# WorkLamp.net
KiCad netlist of a schematic drawn in Altium Designer
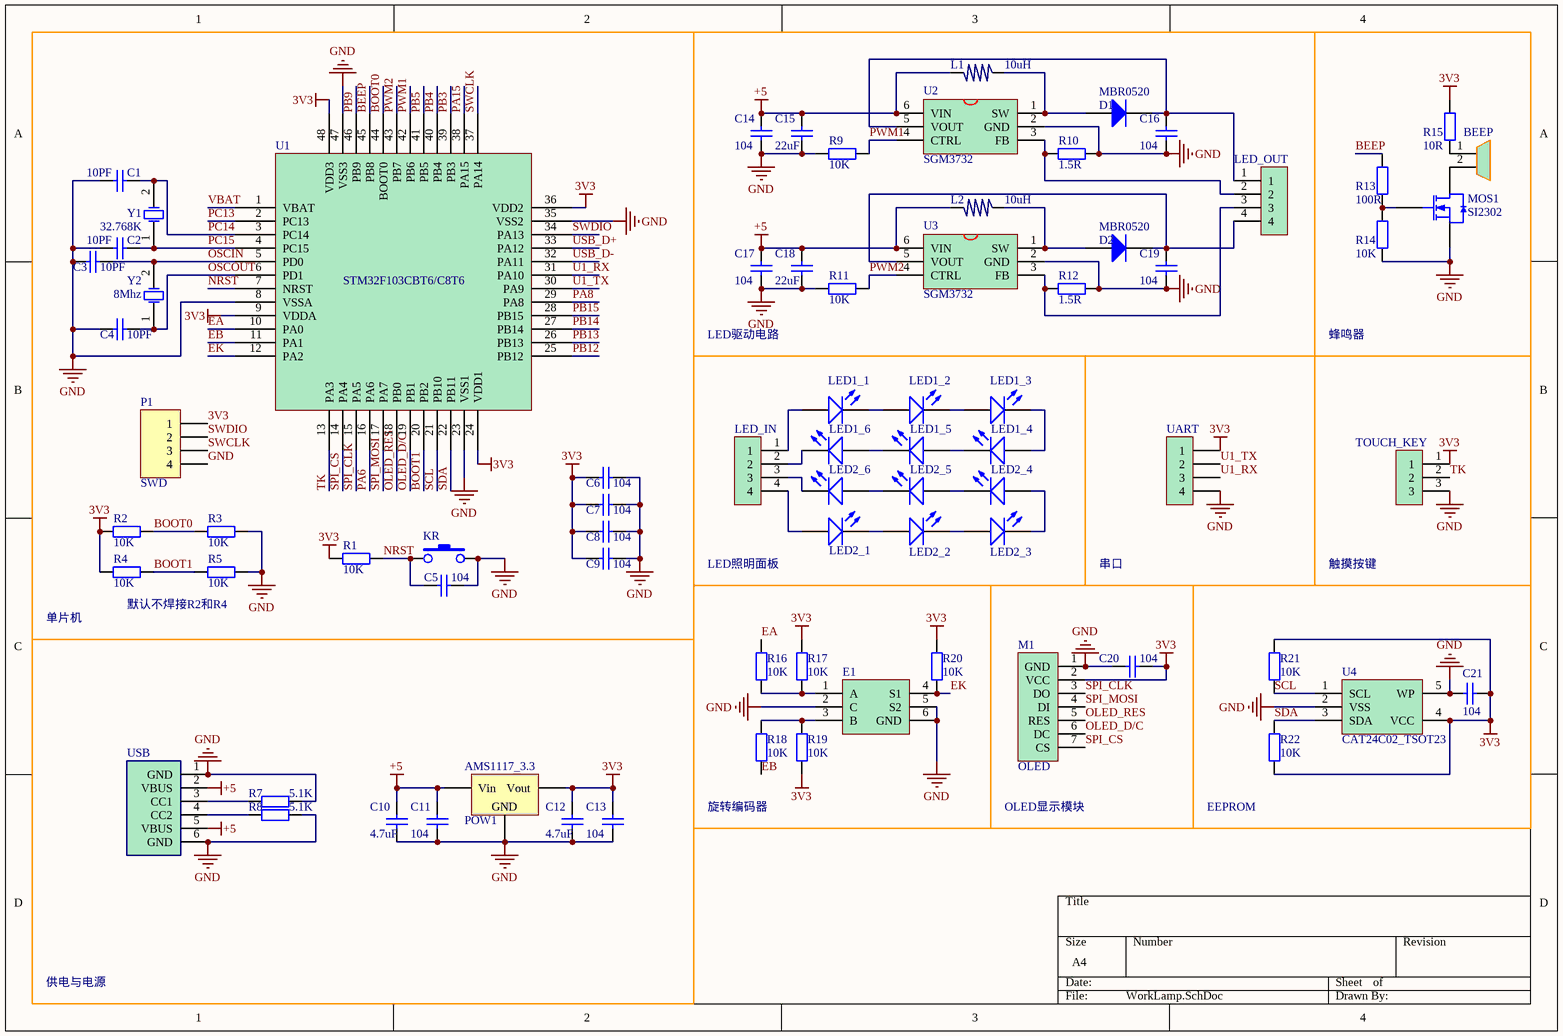
[diagram p0: WorkLamp.SchDoc]

(export (version "E")
  (design (tool "Eeschema 10.0.6"))
  (components
    (comp (ref "BEEP")
      (value "BEEP_5020_SMT")
      (footprint "BEEP_5020_SMT")
      (libsource (lib "MT_Device") (part "BEEP_5020_SMT"))
    )
    (comp (ref "C1") (value "10PF") (footprint "0603_C") (libsource (lib "MT_Device") (part "0603_CAP")))
    (comp (ref "C2") (value "10PF") (footprint "0603_C") (libsource (lib "MT_Device") (part "0603_CAP")))
    (comp (ref "C3") (value "10PF") (footprint "0603_C") (libsource (lib "MT_Device") (part "0603_CAP")))
    (comp (ref "C4") (value "10PF") (footprint "0603_C") (libsource (lib "MT_Device") (part "0603_CAP")))
    (comp (ref "C5") (value "104") (footprint "0603_C") (libsource (lib "MT_Device") (part "0603_CAP")))
    (comp (ref "C6") (value "104") (footprint "0603_C") (libsource (lib "MT_Device") (part "0603_CAP")))
    (comp (ref "C7") (value "104") (footprint "0603_C") (libsource (lib "MT_Device") (part "0603_CAP")))
    (comp (ref "C8") (value "104") (footprint "0603_C") (libsource (lib "MT_Device") (part "0603_CAP")))
    (comp (ref "C9") (value "104") (footprint "0603_C") (libsource (lib "MT_Device") (part "0603_CAP")))
    (comp (ref "C10") (value "4.7uF") (footprint "0603_C") (libsource (lib "MT_Device") (part "0603_CAP")))
    (comp (ref "C11") (value "104") (footprint "0603_C") (libsource (lib "MT_Device") (part "0603_CAP")))
    (comp (ref "C12") (value "4.7uF") (footprint "0603_C") (libsource (lib "MT_Device") (part "0603_CAP")))
    (comp (ref "C13") (value "104") (footprint "0603_C") (libsource (lib "MT_Device") (part "0603_CAP")))
    (comp (ref "C14") (value "104") (footprint "0603_C") (libsource (lib "MT_Device") (part "0603_CAP")))
    (comp (ref "C15") (value "22uF") (footprint "0603_C") (libsource (lib "MT_Device") (part "0603_CAP")))
    (comp (ref "C16") (value "104") (footprint "0603_C") (libsource (lib "MT_Device") (part "0603_CAP")))
    (comp (ref "C17") (value "104") (footprint "0603_C") (libsource (lib "MT_Device") (part "0603_CAP")))
    (comp (ref "C18") (value "22uF") (footprint "0603_C") (libsource (lib "MT_Device") (part "0603_CAP")))
    (comp (ref "C19") (value "104") (footprint "0603_C") (libsource (lib "MT_Device") (part "0603_CAP")))
    (comp (ref "C20") (value "104") (footprint "0603_C") (libsource (lib "MT_Device") (part "0603_CAP")))
    (comp (ref "C21") (value "104") (footprint "0603_C") (libsource (lib "MT_Device") (part "0603_CAP")))
    (comp (ref "D1")
      (value "MBR0520")
      (footprint "SOD_123")
      (libsource (lib "MT_Device") (part "SOD123_MBR0520"))
    )
    (comp (ref "D2")
      (value "MBR0520")
      (footprint "SOD_123")
      (libsource (lib "MT_Device") (part "SOD123_MBR0520"))
    )
    (comp (ref "E1")
      (value "ENCODER")
      (footprint "ENCODER_EC11_DIP")
      (libsource (lib "MT_Device") (part "ENCODER_EC11_DIP"))
    )
    (comp (ref "KR") (value "KEY_SMT") (footprint "KEY_SMT") (libsource (lib "MT_Device") (part "KEY_SMT")))
    (comp (ref "L1") (value "10uH") (footprint "0630_L") (libsource (lib "MT_Device") (part "0630_L")))
    (comp (ref "L2") (value "10uH") (footprint "0630_L") (libsource (lib "MT_Device") (part "0630_L")))
    (comp (ref "LED1_1")
      (value "LED_5730")
      (footprint "LED_5730")
      (description "LED 5730")
      (libsource (lib "MT_Device") (part "LED_5730"))
    )
    (comp (ref "LED1_2")
      (value "LED_5730")
      (footprint "LED_5730")
      (description "LED 5730")
      (libsource (lib "MT_Device") (part "LED_5730"))
    )
    (comp (ref "LED1_3")
      (value "LED_5730")
      (footprint "LED_5730")
      (description "LED 5730")
      (libsource (lib "MT_Device") (part "LED_5730"))
    )
    (comp (ref "LED1_4")
      (value "LED_5730")
      (footprint "LED_5730")
      (description "LED 5730")
      (libsource (lib "MT_Device") (part "LED_5730"))
    )
    (comp (ref "LED1_5")
      (value "LED_5730")
      (footprint "LED_5730")
      (description "LED 5730")
      (libsource (lib "MT_Device") (part "LED_5730"))
    )
    (comp (ref "LED1_6")
      (value "LED_5730")
      (footprint "LED_5730")
      (description "LED 5730")
      (libsource (lib "MT_Device") (part "LED_5730"))
    )
    (comp (ref "LED2_1")
      (value "LED_5730")
      (footprint "LED_5730")
      (description "LED 5730")
      (libsource (lib "MT_Device") (part "LED_5730"))
    )
    (comp (ref "LED2_2")
      (value "LED_5730")
      (footprint "LED_5730")
      (description "LED 5730")
      (libsource (lib "MT_Device") (part "LED_5730"))
    )
    (comp (ref "LED2_3")
      (value "LED_5730")
      (footprint "LED_5730")
      (description "LED 5730")
      (libsource (lib "MT_Device") (part "LED_5730"))
    )
    (comp (ref "LED2_4")
      (value "LED_5730")
      (footprint "LED_5730")
      (description "LED 5730")
      (libsource (lib "MT_Device") (part "LED_5730"))
    )
    (comp (ref "LED2_5")
      (value "LED_5730")
      (footprint "LED_5730")
      (description "LED 5730")
      (libsource (lib "MT_Device") (part "LED_5730"))
    )
    (comp (ref "LED2_6")
      (value "LED_5730")
      (footprint "LED_5730")
      (description "LED 5730")
      (libsource (lib "MT_Device") (part "LED_5730"))
    )
    (comp (ref "LED_IN")
      (value "SH1.25mm_4P")
      (footprint "SH1.25MM_4P")
      (libsource (lib "MT_Connector") (part "SH1.25mm_4P"))
    )
    (comp (ref "LED_OUT")
      (value "SH1.25mm_4P")
      (footprint "SH1.25MM_4P")
      (libsource (lib "") (part "SH1.25mm_4P_1"))
    )
    (comp (ref "M1")
      (value "OLED")
      (footprint "OLED_0.96_SPI")
      (libsource (lib "MT_Module") (part "OLED_0.96_SPI"))
    )
    (comp (ref "MOS1")
      (value "SI2302")
      (footprint "SOT23")
      (libsource (lib "MT_Device") (part "MOSN_SI2302_SOT23"))
    )
    (comp (ref "P1")
      (value "SWD")
      (footprint "HDR1X4")
      (description "Header, 4-Pin")
      (fields (field (name "PUBLISHER") "Altium Limited"))
      (libsource (lib "Miscellaneous Connectors") (part "Header 4"))
    )
    (comp (ref "POW1")
      (value "AMS1117_3.3")
      (footprint "SOT223")
      (libsource (lib "MT_Device") (part "AMS1117_3.3"))
    )
    (comp (ref "R1") (value "10K") (footprint "0603_R") (libsource (lib "") (part "0603_RES_2")))
    (comp (ref "R2") (value "10K") (footprint "0603_R") (libsource (lib "MT_Device") (part "0603_RES")))
    (comp (ref "R3") (value "10K") (footprint "0603_R") (libsource (lib "MT_Device") (part "0603_RES")))
    (comp (ref "R4") (value "10K") (footprint "0603_R") (libsource (lib "MT_Device") (part "0603_RES")))
    (comp (ref "R5") (value "10K") (footprint "0603_R") (libsource (lib "MT_Device") (part "0603_RES")))
    (comp (ref "R7") (value "5.1K") (footprint "0603_R") (libsource (lib "MT_Device") (part "0603_RES")))
    (comp (ref "R8") (value "5.1K") (footprint "0603_R") (libsource (lib "MT_Device") (part "0603_RES")))
    (comp (ref "R9") (value "10K") (footprint "0603_R") (libsource (lib "") (part "0603_RES_2")))
    (comp (ref "R10") (value "1.5R") (footprint "0603_R") (libsource (lib "MT_Device") (part "0603_RES")))
    (comp (ref "R11") (value "10K") (footprint "0603_R") (libsource (lib "") (part "0603_RES_2")))
    (comp (ref "R12") (value "1.5R") (footprint "0603_R") (libsource (lib "MT_Device") (part "0603_RES")))
    (comp (ref "R13") (value "100R") (footprint "0603_R") (libsource (lib "") (part "0603_RES_1")))
    (comp (ref "R14") (value "10K") (footprint "0603_R") (libsource (lib "") (part "0603_RES_1")))
    (comp (ref "R15") (value "10R") (footprint "0603_R") (libsource (lib "") (part "0603_RES_3")))
    (comp (ref "R16") (value "10K") (footprint "0603_R") (libsource (lib "") (part "0603_RES_1")))
    (comp (ref "R17") (value "10K") (footprint "0603_R") (libsource (lib "") (part "0603_RES_1")))
    (comp (ref "R18") (value "10K") (footprint "0603_R") (libsource (lib "") (part "0603_RES_1")))
    (comp (ref "R19") (value "10K") (footprint "0603_R") (libsource (lib "") (part "0603_RES_1")))
    (comp (ref "R20") (value "10K") (footprint "0603_R") (libsource (lib "") (part "0603_RES_1")))
    (comp (ref "R21") (value "10K") (footprint "0603_R") (libsource (lib "") (part "0603_RES_1")))
    (comp (ref "R22") (value "10K") (footprint "0603_R") (libsource (lib "") (part "0603_RES_1")))
    (comp (ref "TOUCH_KEY")
      (value "SH1.25mm_3P")
      (footprint "SH1.25mm_3P")
      (libsource (lib "MT_Connector") (part "SH1.25mm_3P"))
    )
    (comp (ref "U1")
      (value "STM32F103C8T6")
      (footprint "LQFP48")
      (libsource (lib "MT_Chip") (part "STM32F103C8T6"))
    )
    (comp (ref "U2")
      (value "SGM3732")
      (footprint "TSOT_23_6")
      (description "PWM Dimming, 38V Step-Up LED Driver")
      (libsource (lib "MT_Chip") (part "SGM3732"))
    )
    (comp (ref "U3")
      (value "SGM3732")
      (footprint "TSOT_23_6")
      (description "PWM Dimming, 38V Step-Up LED Driver")
      (libsource (lib "MT_Chip") (part "SGM3732"))
    )
    (comp (ref "U4")
      (value "CAT24C02_TSOT23")
      (footprint "SOT_23_5")
      (libsource (lib "MT_Chip") (part "CAT24C02_TSOT23"))
    )
    (comp (ref "UART")
      (value "Header_2.54_4P")
      (footprint "HDR1_4P")
      (libsource (lib "MT_Connector") (part "Header_2.54_4P"))
    )
    (comp (ref "USB")
      (value "USB_C_6P_SMT_S1")
      (footprint "USB_C_6PIN_SMT_S1")
      (libsource (lib "MT_Device") (part "USB_C_6P_SMT_S1"))
    )
    (comp (ref "Y1")
      (value "32.768K")
      (footprint "XTAL_32.768_3215_2")
      (libsource (lib "MT_Device") (part "XTAL_32.768_3215_2"))
    )
    (comp (ref "Y2")
      (value "8Mhz")
      (footprint "XTAL_5032_2")
      (libsource (lib "MT_Device") (part "XTAL_8MHz_5032_2"))
    )
  )
  (nets
    (net (code "1") (name "+5") (class "Default")
      (node (ref "C10") (pin "1") (pinfunction "1_1") (pintype "passive"))
      (node (ref "C11") (pin "1") (pinfunction "1_1") (pintype "passive"))
      (node (ref "C14") (pin "1") (pinfunction "1_1") (pintype "passive"))
      (node (ref "C15") (pin "1") (pinfunction "1_1") (pintype "passive"))
      (node (ref "C17") (pin "1") (pinfunction "1_1") (pintype "passive"))
      (node (ref "C18") (pin "1") (pinfunction "1_1") (pintype "passive"))
      (node (ref "L1") (pin "2") (pintype "passive"))
      (node (ref "L2") (pin "2") (pintype "passive"))
      (node (ref "POW1") (pin "3") (pinfunction "Vin_3") (pintype "passive"))
      (node (ref "U2") (pin "6") (pinfunction "VIN_6") (pintype "passive"))
      (node (ref "U3") (pin "6") (pinfunction "VIN_6") (pintype "passive"))
      (node (ref "USB") (pin "2") (pinfunction "VBUS_2") (pintype "passive"))
      (node (ref "USB") (pin "5") (pinfunction "VBUS_5") (pintype "passive"))
    )
    (net (code "2") (name "/BEEP") (class "Default")
      (node (ref "R13") (pin "2") (pinfunction "2_2") (pintype "passive"))
      (node (ref "U1") (pin "45") (pinfunction "PB8_45") (pintype "passive"))
    )
    (net (code "3") (name "/BOOT0") (class "Default")
      (node (ref "R2") (pin "1") (pinfunction "1_1") (pintype "passive"))
      (node (ref "R3") (pin "2") (pinfunction "2_2") (pintype "passive"))
      (node (ref "U1") (pin "44") (pinfunction "BOOT0_44") (pintype "passive"))
    )
    (net (code "4") (name "/BOOT1") (class "Default")
      (node (ref "R4") (pin "1") (pinfunction "1_1") (pintype "passive"))
      (node (ref "R5") (pin "2") (pinfunction "2_2") (pintype "passive"))
      (node (ref "U1") (pin "20") (pinfunction "PB2_20") (pintype "passive"))
    )
    (net (code "5") (name "/EA") (class "Default")
      (node (ref "R16") (pin "2") (pinfunction "2_2") (pintype "passive"))
      (node (ref "U1") (pin "10") (pinfunction "PA0_10") (pintype "passive"))
    )
    (net (code "6") (name "/EB") (class "Default")
      (node (ref "R18") (pin "1") (pinfunction "1_1") (pintype "passive"))
      (node (ref "U1") (pin "11") (pinfunction "PA1_11") (pintype "passive"))
    )
    (net (code "7") (name "/EK") (class "Default")
      (node (ref "E1") (pin "4") (pinfunction "S1_4") (pintype "passive"))
      (node (ref "R20") (pin "1") (pinfunction "1_1") (pintype "passive"))
      (node (ref "U1") (pin "12") (pinfunction "PA2_12") (pintype "passive"))
    )
    (net (code "8") (name "/NRST") (class "Default")
      (node (ref "C5") (pin "2") (pinfunction "2_2") (pintype "passive"))
      (node (ref "KR") (pin "1") (pinfunction "1_1") (pintype "passive"))
      (node (ref "R1") (pin "2") (pinfunction "2_2") (pintype "passive"))
      (node (ref "U1") (pin "7") (pinfunction "NRST_7") (pintype "passive"))
    )
    (net (code "9") (name "/OLED_D{slash}C") (class "Default")
      (node (ref "M1") (pin "6") (pinfunction "DC_6") (pintype "passive"))
      (node (ref "U1") (pin "19") (pinfunction "PB1_19") (pintype "passive"))
    )
    (net (code "10") (name "/OLED_RES") (class "Default")
      (node (ref "M1") (pin "5") (pinfunction "RES_5") (pintype "passive"))
      (node (ref "U1") (pin "18") (pinfunction "PB0_18") (pintype "passive"))
    )
    (net (code "11") (name "/OSCIN") (class "Default")
      (node (ref "C3") (pin "2") (pinfunction "2_2") (pintype "passive"))
      (node (ref "U1") (pin "5") (pinfunction "PD0_5") (pintype "passive"))
      (node (ref "Y2") (pin "2") (pinfunction "OSC2_2") (pintype "passive"))
    )
    (net (code "12") (name "/OSCOUT") (class "Default")
      (node (ref "C4") (pin "2") (pinfunction "2_2") (pintype "passive"))
      (node (ref "U1") (pin "6") (pinfunction "PD1_6") (pintype "passive"))
      (node (ref "Y2") (pin "1") (pinfunction "OSC1_1") (pintype "passive"))
    )
    (net (code "13") (name "/PA6") (class "Default")
      (node (ref "U1") (pin "16") (pinfunction "PA6_16") (pintype "passive"))
    )
    (net (code "14") (name "/PA8") (class "Default")
      (node (ref "U1") (pin "29") (pinfunction "PA8_29") (pintype "passive"))
    )
    (net (code "15") (name "/PA15") (class "Default")
      (node (ref "U1") (pin "38") (pinfunction "PA15_38") (pintype "passive"))
    )
    (net (code "16") (name "/PB3") (class "Default")
      (node (ref "U1") (pin "39") (pinfunction "PB3_39") (pintype "passive"))
    )
    (net (code "17") (name "/PB4") (class "Default")
      (node (ref "U1") (pin "40") (pinfunction "PB4_40") (pintype "passive"))
    )
    (net (code "18") (name "/PB5") (class "Default")
      (node (ref "U1") (pin "41") (pinfunction "PB5_41") (pintype "passive"))
    )
    (net (code "19") (name "/PB9") (class "Default")
      (node (ref "U1") (pin "46") (pinfunction "PB9_46") (pintype "passive"))
    )
    (net (code "20") (name "/PB12") (class "Default")
      (node (ref "U1") (pin "25") (pinfunction "PB12_25") (pintype "passive"))
    )
    (net (code "21") (name "/PB13") (class "Default")
      (node (ref "U1") (pin "26") (pinfunction "PB13_26") (pintype "passive"))
    )
    (net (code "22") (name "/PB14") (class "Default")
      (node (ref "U1") (pin "27") (pinfunction "PB14_27") (pintype "passive"))
    )
    (net (code "23") (name "/PB15") (class "Default")
      (node (ref "U1") (pin "28") (pinfunction "PB15_28") (pintype "passive"))
    )
    (net (code "24") (name "/PC13") (class "Default")
      (node (ref "U1") (pin "2") (pinfunction "PC13_2") (pintype "passive"))
    )
    (net (code "25") (name "/PC14") (class "Default")
      (node (ref "C1") (pin "2") (pinfunction "2_2") (pintype "passive"))
      (node (ref "U1") (pin "3") (pinfunction "PC14_3") (pintype "passive"))
      (node (ref "Y1") (pin "2") (pinfunction "OSC2_2") (pintype "passive"))
    )
    (net (code "26") (name "/PC15") (class "Default")
      (node (ref "C2") (pin "2") (pinfunction "2_2") (pintype "passive"))
      (node (ref "U1") (pin "4") (pinfunction "PC15_4") (pintype "passive"))
      (node (ref "Y1") (pin "1") (pinfunction "OSC1_1") (pintype "passive"))
    )
    (net (code "27") (name "/PWM1") (class "Default")
      (node (ref "R9") (pin "2") (pinfunction "2_2") (pintype "passive"))
      (node (ref "U1") (pin "42") (pinfunction "PB6_42") (pintype "passive"))
      (node (ref "U2") (pin "4") (pinfunction "CTRL_4") (pintype "passive"))
    )
    (net (code "28") (name "/PWM2") (class "Default")
      (node (ref "R11") (pin "2") (pinfunction "2_2") (pintype "passive"))
      (node (ref "U1") (pin "43") (pinfunction "PB7_43") (pintype "passive"))
      (node (ref "U3") (pin "4") (pinfunction "CTRL_4") (pintype "passive"))
    )
    (net (code "29") (name "/SCL") (class "Default")
      (node (ref "R21") (pin "1") (pinfunction "1_1") (pintype "passive"))
      (node (ref "U1") (pin "21") (pinfunction "PB10_21") (pintype "passive"))
      (node (ref "U4") (pin "1") (pinfunction "SCL_1") (pintype "passive"))
    )
    (net (code "30") (name "/SDA") (class "Default")
      (node (ref "R22") (pin "2") (pinfunction "2_2") (pintype "passive"))
      (node (ref "U1") (pin "22") (pinfunction "PB11_22") (pintype "passive"))
      (node (ref "U4") (pin "3") (pinfunction "SDA_3") (pintype "passive"))
    )
    (net (code "31") (name "/SPI_CLK") (class "Default")
      (node (ref "M1") (pin "3") (pinfunction "DO_3") (pintype "passive"))
      (node (ref "U1") (pin "15") (pinfunction "PA5_15") (pintype "passive"))
    )
    (net (code "32") (name "/SPI_CS") (class "Default")
      (node (ref "M1") (pin "7") (pinfunction "CS_7") (pintype "passive"))
      (node (ref "U1") (pin "14") (pinfunction "PA4_14") (pintype "passive"))
    )
    (net (code "33") (name "/SPI_MOSI") (class "Default")
      (node (ref "M1") (pin "4") (pinfunction "DI_4") (pintype "passive"))
      (node (ref "U1") (pin "17") (pinfunction "PA7_17") (pintype "passive"))
    )
    (net (code "34") (name "/SWCLK") (class "Default")
      (node (ref "P1") (pin "3") (pinfunction "3_3") (pintype "passive"))
      (node (ref "U1") (pin "37") (pinfunction "PA14_37") (pintype "passive"))
    )
    (net (code "35") (name "/SWDIO") (class "Default")
      (node (ref "P1") (pin "2") (pinfunction "2_2") (pintype "passive"))
      (node (ref "U1") (pin "34") (pinfunction "PA13_34") (pintype "passive"))
    )
    (net (code "36") (name "/TK") (class "Default")
      (node (ref "TOUCH_KEY") (pin "2") (pinfunction "2_2") (pintype "passive"))
      (node (ref "U1") (pin "13") (pinfunction "PA3_13") (pintype "passive"))
    )
    (net (code "37") (name "/U1_RX") (class "Default")
      (node (ref "U1") (pin "31") (pinfunction "PA10_31") (pintype "passive"))
      (node (ref "UART") (pin "3") (pinfunction "3_3") (pintype "passive"))
    )
    (net (code "38") (name "/U1_TX") (class "Default")
      (node (ref "U1") (pin "30") (pinfunction "PA9_30") (pintype "passive"))
      (node (ref "UART") (pin "2") (pinfunction "2_2") (pintype "passive"))
    )
    (net (code "39") (name "/USB_D+") (class "Default")
      (node (ref "U1") (pin "33") (pinfunction "PA12_33") (pintype "passive"))
    )
    (net (code "40") (name "/USB_D-") (class "Default")
      (node (ref "U1") (pin "32") (pinfunction "PA11_32") (pintype "passive"))
    )
    (net (code "41") (name "/VBAT") (class "Default")
      (node (ref "U1") (pin "1") (pinfunction "VBAT_1") (pintype "passive"))
    )
    (net (code "42") (name "3V3") (class "Default")
      (node (ref "C12") (pin "1") (pinfunction "1_1") (pintype "passive"))
      (node (ref "C13") (pin "1") (pinfunction "1_1") (pintype "passive"))
      (node (ref "C20") (pin "1") (pinfunction "1_1") (pintype "passive"))
      (node (ref "C21") (pin "1") (pinfunction "1_1") (pintype "passive"))
      (node (ref "C6") (pin "2") (pinfunction "2_2") (pintype "passive"))
      (node (ref "C7") (pin "2") (pinfunction "2_2") (pintype "passive"))
      (node (ref "C8") (pin "2") (pinfunction "2_2") (pintype "passive"))
      (node (ref "C9") (pin "2") (pinfunction "2_2") (pintype "passive"))
      (node (ref "M1") (pin "2") (pinfunction "VCC_2") (pintype "passive"))
      (node (ref "P1") (pin "1") (pinfunction "1_1") (pintype "passive"))
      (node (ref "POW1") (pin "2") (pinfunction "Vout_2") (pintype "passive"))
      (node (ref "R1") (pin "1") (pinfunction "1_1") (pintype "passive"))
      (node (ref "R15") (pin "1") (pinfunction "1_1") (pintype "passive"))
      (node (ref "R17") (pin "2") (pinfunction "2_2") (pintype "passive"))
      (node (ref "R19") (pin "1") (pinfunction "1_1") (pintype "passive"))
      (node (ref "R2") (pin "2") (pinfunction "2_2") (pintype "passive"))
      (node (ref "R20") (pin "2") (pinfunction "2_2") (pintype "passive"))
      (node (ref "R21") (pin "2") (pinfunction "2_2") (pintype "passive"))
      (node (ref "R22") (pin "1") (pinfunction "1_1") (pintype "passive"))
      (node (ref "R4") (pin "2") (pinfunction "2_2") (pintype "passive"))
      (node (ref "TOUCH_KEY") (pin "1") (pinfunction "1_1") (pintype "passive"))
      (node (ref "U1") (pin "24") (pinfunction "VDD1_24") (pintype "passive"))
      (node (ref "U1") (pin "36") (pinfunction "VDD2_36") (pintype "passive"))
      (node (ref "U1") (pin "48") (pinfunction "VDD3_48") (pintype "passive"))
      (node (ref "U1") (pin "9") (pinfunction "VDDA_9") (pintype "passive"))
      (node (ref "U4") (pin "4") (pinfunction "VCC_4") (pintype "passive"))
      (node (ref "UART") (pin "1") (pinfunction "1_1") (pintype "passive"))
    )
    (net (code "43") (name "GND") (class "Default")
      (node (ref "C1") (pin "1") (pinfunction "1_1") (pintype "passive"))
      (node (ref "C10") (pin "2") (pinfunction "2_2") (pintype "passive"))
      (node (ref "C11") (pin "2") (pinfunction "2_2") (pintype "passive"))
      (node (ref "C12") (pin "2") (pinfunction "2_2") (pintype "passive"))
      (node (ref "C13") (pin "2") (pinfunction "2_2") (pintype "passive"))
      (node (ref "C14") (pin "2") (pinfunction "2_2") (pintype "passive"))
      (node (ref "C15") (pin "2") (pinfunction "2_2") (pintype "passive"))
      (node (ref "C16") (pin "2") (pinfunction "2_2") (pintype "passive"))
      (node (ref "C17") (pin "2") (pinfunction "2_2") (pintype "passive"))
      (node (ref "C18") (pin "2") (pinfunction "2_2") (pintype "passive"))
      (node (ref "C19") (pin "2") (pinfunction "2_2") (pintype "passive"))
      (node (ref "C2") (pin "1") (pinfunction "1_1") (pintype "passive"))
      (node (ref "C20") (pin "2") (pinfunction "2_2") (pintype "passive"))
      (node (ref "C21") (pin "2") (pinfunction "2_2") (pintype "passive"))
      (node (ref "C3") (pin "1") (pinfunction "1_1") (pintype "passive"))
      (node (ref "C4") (pin "1") (pinfunction "1_1") (pintype "passive"))
      (node (ref "C5") (pin "1") (pinfunction "1_1") (pintype "passive"))
      (node (ref "C6") (pin "1") (pinfunction "1_1") (pintype "passive"))
      (node (ref "C7") (pin "1") (pinfunction "1_1") (pintype "passive"))
      (node (ref "C8") (pin "1") (pinfunction "1_1") (pintype "passive"))
      (node (ref "C9") (pin "1") (pinfunction "1_1") (pintype "passive"))
      (node (ref "E1") (pin "2") (pinfunction "C_2") (pintype "passive"))
      (node (ref "E1") (pin "5") (pinfunction "S2_5") (pintype "passive"))
      (node (ref "E1") (pin "6") (pinfunction "GND_6") (pintype "passive"))
      (node (ref "KR") (pin "2") (pinfunction "2_2") (pintype "passive"))
      (node (ref "M1") (pin "1") (pinfunction "GND_1") (pintype "passive"))
      (node (ref "MOS1") (pin "2") (pinfunction "S_2") (pintype "passive"))
      (node (ref "P1") (pin "4") (pinfunction "4_4") (pintype "passive"))
      (node (ref "POW1") (pin "1") (pinfunction "GND_1") (pintype "passive"))
      (node (ref "R10") (pin "1") (pinfunction "1_1") (pintype "passive"))
      (node (ref "R11") (pin "1") (pinfunction "1_1") (pintype "passive"))
      (node (ref "R12") (pin "1") (pinfunction "1_1") (pintype "passive"))
      (node (ref "R14") (pin "1") (pinfunction "1_1") (pintype "passive"))
      (node (ref "R3") (pin "1") (pinfunction "1_1") (pintype "passive"))
      (node (ref "R5") (pin "1") (pinfunction "1_1") (pintype "passive"))
      (node (ref "R7") (pin "1") (pinfunction "1_1") (pintype "passive"))
      (node (ref "R8") (pin "1") (pinfunction "1_1") (pintype "passive"))
      (node (ref "R9") (pin "1") (pinfunction "1_1") (pintype "passive"))
      (node (ref "TOUCH_KEY") (pin "3") (pinfunction "3_3") (pintype "passive"))
      (node (ref "U1") (pin "23") (pinfunction "VSS1_23") (pintype "passive"))
      (node (ref "U1") (pin "35") (pinfunction "VSS2_35") (pintype "passive"))
      (node (ref "U1") (pin "47") (pinfunction "VSS3_47") (pintype "passive"))
      (node (ref "U1") (pin "8") (pinfunction "VSSA_8") (pintype "passive"))
      (node (ref "U2") (pin "2") (pinfunction "GND_2") (pintype "passive"))
      (node (ref "U3") (pin "2") (pinfunction "GND_2") (pintype "passive"))
      (node (ref "U4") (pin "2") (pinfunction "VSS_2") (pintype "passive"))
      (node (ref "U4") (pin "5") (pinfunction "WP_5") (pintype "passive"))
      (node (ref "UART") (pin "4") (pinfunction "4_4") (pintype "passive"))
      (node (ref "USB") (pin "1") (pinfunction "GND_1") (pintype "passive"))
      (node (ref "USB") (pin "6") (pinfunction "GND_6") (pintype "passive"))
    )
    (net (code "44") (name "Net-(BEEP-Pad1)") (class "Default")
      (node (ref "BEEP") (pin "1") (pinfunction "1_1") (pintype "passive"))
      (node (ref "R15") (pin "2") (pinfunction "2_2") (pintype "passive"))
    )
    (net (code "45") (name "Net-(D1-A)") (class "Default")
      (node (ref "D1") (pin "1") (pinfunction "A_1") (pintype "passive"))
      (node (ref "L1") (pin "1") (pintype "passive"))
      (node (ref "U2") (pin "1") (pinfunction "SW_1") (pintype "passive"))
    )
    (net (code "46") (name "Net-(D1-K)") (class "Default")
      (node (ref "C16") (pin "1") (pinfunction "1_1") (pintype "passive"))
      (node (ref "D1") (pin "2") (pinfunction "K_2") (pintype "passive"))
      (node (ref "LED_OUT") (pin "1") (pinfunction "1_1") (pintype "passive"))
      (node (ref "U2") (pin "5") (pinfunction "VOUT_5") (pintype "passive"))
    )
    (net (code "47") (name "Net-(D2-A)") (class "Default")
      (node (ref "D2") (pin "1") (pinfunction "A_1") (pintype "passive"))
      (node (ref "L2") (pin "1") (pintype "passive"))
      (node (ref "U3") (pin "1") (pinfunction "SW_1") (pintype "passive"))
    )
    (net (code "48") (name "Net-(D2-K)") (class "Default")
      (node (ref "C19") (pin "1") (pinfunction "1_1") (pintype "passive"))
      (node (ref "D2") (pin "2") (pinfunction "K_2") (pintype "passive"))
      (node (ref "LED_OUT") (pin "4") (pinfunction "4_4") (pintype "passive"))
      (node (ref "U3") (pin "5") (pinfunction "VOUT_5") (pintype "passive"))
    )
    (net (code "49") (name "Net-(E1-A)") (class "Default")
      (node (ref "E1") (pin "1") (pinfunction "A_1") (pintype "passive"))
      (node (ref "R16") (pin "1") (pinfunction "1_1") (pintype "passive"))
      (node (ref "R17") (pin "1") (pinfunction "1_1") (pintype "passive"))
    )
    (net (code "50") (name "Net-(E1-B)") (class "Default")
      (node (ref "E1") (pin "3") (pinfunction "B_3") (pintype "passive"))
      (node (ref "R18") (pin "2") (pinfunction "2_2") (pintype "passive"))
      (node (ref "R19") (pin "2") (pinfunction "2_2") (pintype "passive"))
    )
    (net (code "51") (name "Net-(LED1_1-A)") (class "Default")
      (node (ref "LED1_1") (pin "2") (pinfunction "A_2") (pintype "passive"))
      (node (ref "LED_IN") (pin "1") (pinfunction "1_1") (pintype "passive"))
    )
    (net (code "52") (name "Net-(LED1_1-K)") (class "Default")
      (node (ref "LED1_1") (pin "1") (pinfunction "K_1") (pintype "passive"))
      (node (ref "LED1_2") (pin "2") (pinfunction "A_2") (pintype "passive"))
    )
    (net (code "53") (name "Net-(LED1_2-K)") (class "Default")
      (node (ref "LED1_2") (pin "1") (pinfunction "K_1") (pintype "passive"))
      (node (ref "LED1_3") (pin "2") (pinfunction "A_2") (pintype "passive"))
    )
    (net (code "54") (name "Net-(LED1_3-K)") (class "Default")
      (node (ref "LED1_3") (pin "1") (pinfunction "K_1") (pintype "passive"))
      (node (ref "LED1_4") (pin "2") (pinfunction "A_2") (pintype "passive"))
    )
    (net (code "55") (name "Net-(LED1_4-K)") (class "Default")
      (node (ref "LED1_4") (pin "1") (pinfunction "K_1") (pintype "passive"))
      (node (ref "LED1_5") (pin "2") (pinfunction "A_2") (pintype "passive"))
    )
    (net (code "56") (name "Net-(LED1_5-K)") (class "Default")
      (node (ref "LED1_5") (pin "1") (pinfunction "K_1") (pintype "passive"))
      (node (ref "LED1_6") (pin "2") (pinfunction "A_2") (pintype "passive"))
    )
    (net (code "57") (name "Net-(LED1_6-K)") (class "Default")
      (node (ref "LED1_6") (pin "1") (pinfunction "K_1") (pintype "passive"))
      (node (ref "LED_IN") (pin "2") (pinfunction "2_2") (pintype "passive"))
    )
    (net (code "58") (name "Net-(LED2_1-A)") (class "Default")
      (node (ref "LED2_1") (pin "2") (pinfunction "A_2") (pintype "passive"))
      (node (ref "LED_IN") (pin "4") (pinfunction "4_4") (pintype "passive"))
    )
    (net (code "59") (name "Net-(LED2_1-K)") (class "Default")
      (node (ref "LED2_1") (pin "1") (pinfunction "K_1") (pintype "passive"))
      (node (ref "LED2_2") (pin "2") (pinfunction "A_2") (pintype "passive"))
    )
    (net (code "60") (name "Net-(LED2_2-K)") (class "Default")
      (node (ref "LED2_2") (pin "1") (pinfunction "K_1") (pintype "passive"))
      (node (ref "LED2_3") (pin "2") (pinfunction "A_2") (pintype "passive"))
    )
    (net (code "61") (name "Net-(LED2_3-K)") (class "Default")
      (node (ref "LED2_3") (pin "1") (pinfunction "K_1") (pintype "passive"))
      (node (ref "LED2_4") (pin "2") (pinfunction "A_2") (pintype "passive"))
    )
    (net (code "62") (name "Net-(LED2_4-K)") (class "Default")
      (node (ref "LED2_4") (pin "1") (pinfunction "K_1") (pintype "passive"))
      (node (ref "LED2_5") (pin "2") (pinfunction "A_2") (pintype "passive"))
    )
    (net (code "63") (name "Net-(LED2_5-K)") (class "Default")
      (node (ref "LED2_5") (pin "1") (pinfunction "K_1") (pintype "passive"))
      (node (ref "LED2_6") (pin "2") (pinfunction "A_2") (pintype "passive"))
    )
    (net (code "64") (name "Net-(LED2_6-K)") (class "Default")
      (node (ref "LED2_6") (pin "1") (pinfunction "K_1") (pintype "passive"))
      (node (ref "LED_IN") (pin "3") (pinfunction "3_3") (pintype "passive"))
    )
    (net (code "65") (name "Net-(MOS1-D)") (class "Default")
      (node (ref "BEEP") (pin "2") (pinfunction "2_2") (pintype "passive"))
      (node (ref "MOS1") (pin "3") (pinfunction "D_3") (pintype "passive"))
    )
    (net (code "66") (name "Net-(MOS1-G)") (class "Default")
      (node (ref "MOS1") (pin "1") (pinfunction "G_1") (pintype "passive"))
      (node (ref "R13") (pin "1") (pinfunction "1_1") (pintype "passive"))
      (node (ref "R14") (pin "2") (pinfunction "2_2") (pintype "passive"))
    )
    (net (code "67") (name "Net-(U2-FB)") (class "Default")
      (node (ref "LED_OUT") (pin "2") (pinfunction "2_2") (pintype "passive"))
      (node (ref "R10") (pin "2") (pinfunction "2_2") (pintype "passive"))
      (node (ref "U2") (pin "3") (pinfunction "FB_3") (pintype "passive"))
    )
    (net (code "68") (name "Net-(U3-FB)") (class "Default")
      (node (ref "LED_OUT") (pin "3") (pinfunction "3_3") (pintype "passive"))
      (node (ref "R12") (pin "2") (pinfunction "2_2") (pintype "passive"))
      (node (ref "U3") (pin "3") (pinfunction "FB_3") (pintype "passive"))
    )
    (net (code "69") (name "Net-(USB-CC1)") (class "Default")
      (node (ref "R7") (pin "2") (pinfunction "2_2") (pintype "passive"))
      (node (ref "USB") (pin "3") (pinfunction "CC1_3") (pintype "passive"))
    )
    (net (code "70") (name "Net-(USB-CC2)") (class "Default")
      (node (ref "R8") (pin "2") (pinfunction "2_2") (pintype "passive"))
      (node (ref "USB") (pin "4") (pinfunction "CC2_4") (pintype "passive"))
    )
  )
)
